# EtherIOv3.net
KiCad netlist of a schematic drawn in Altium Designer
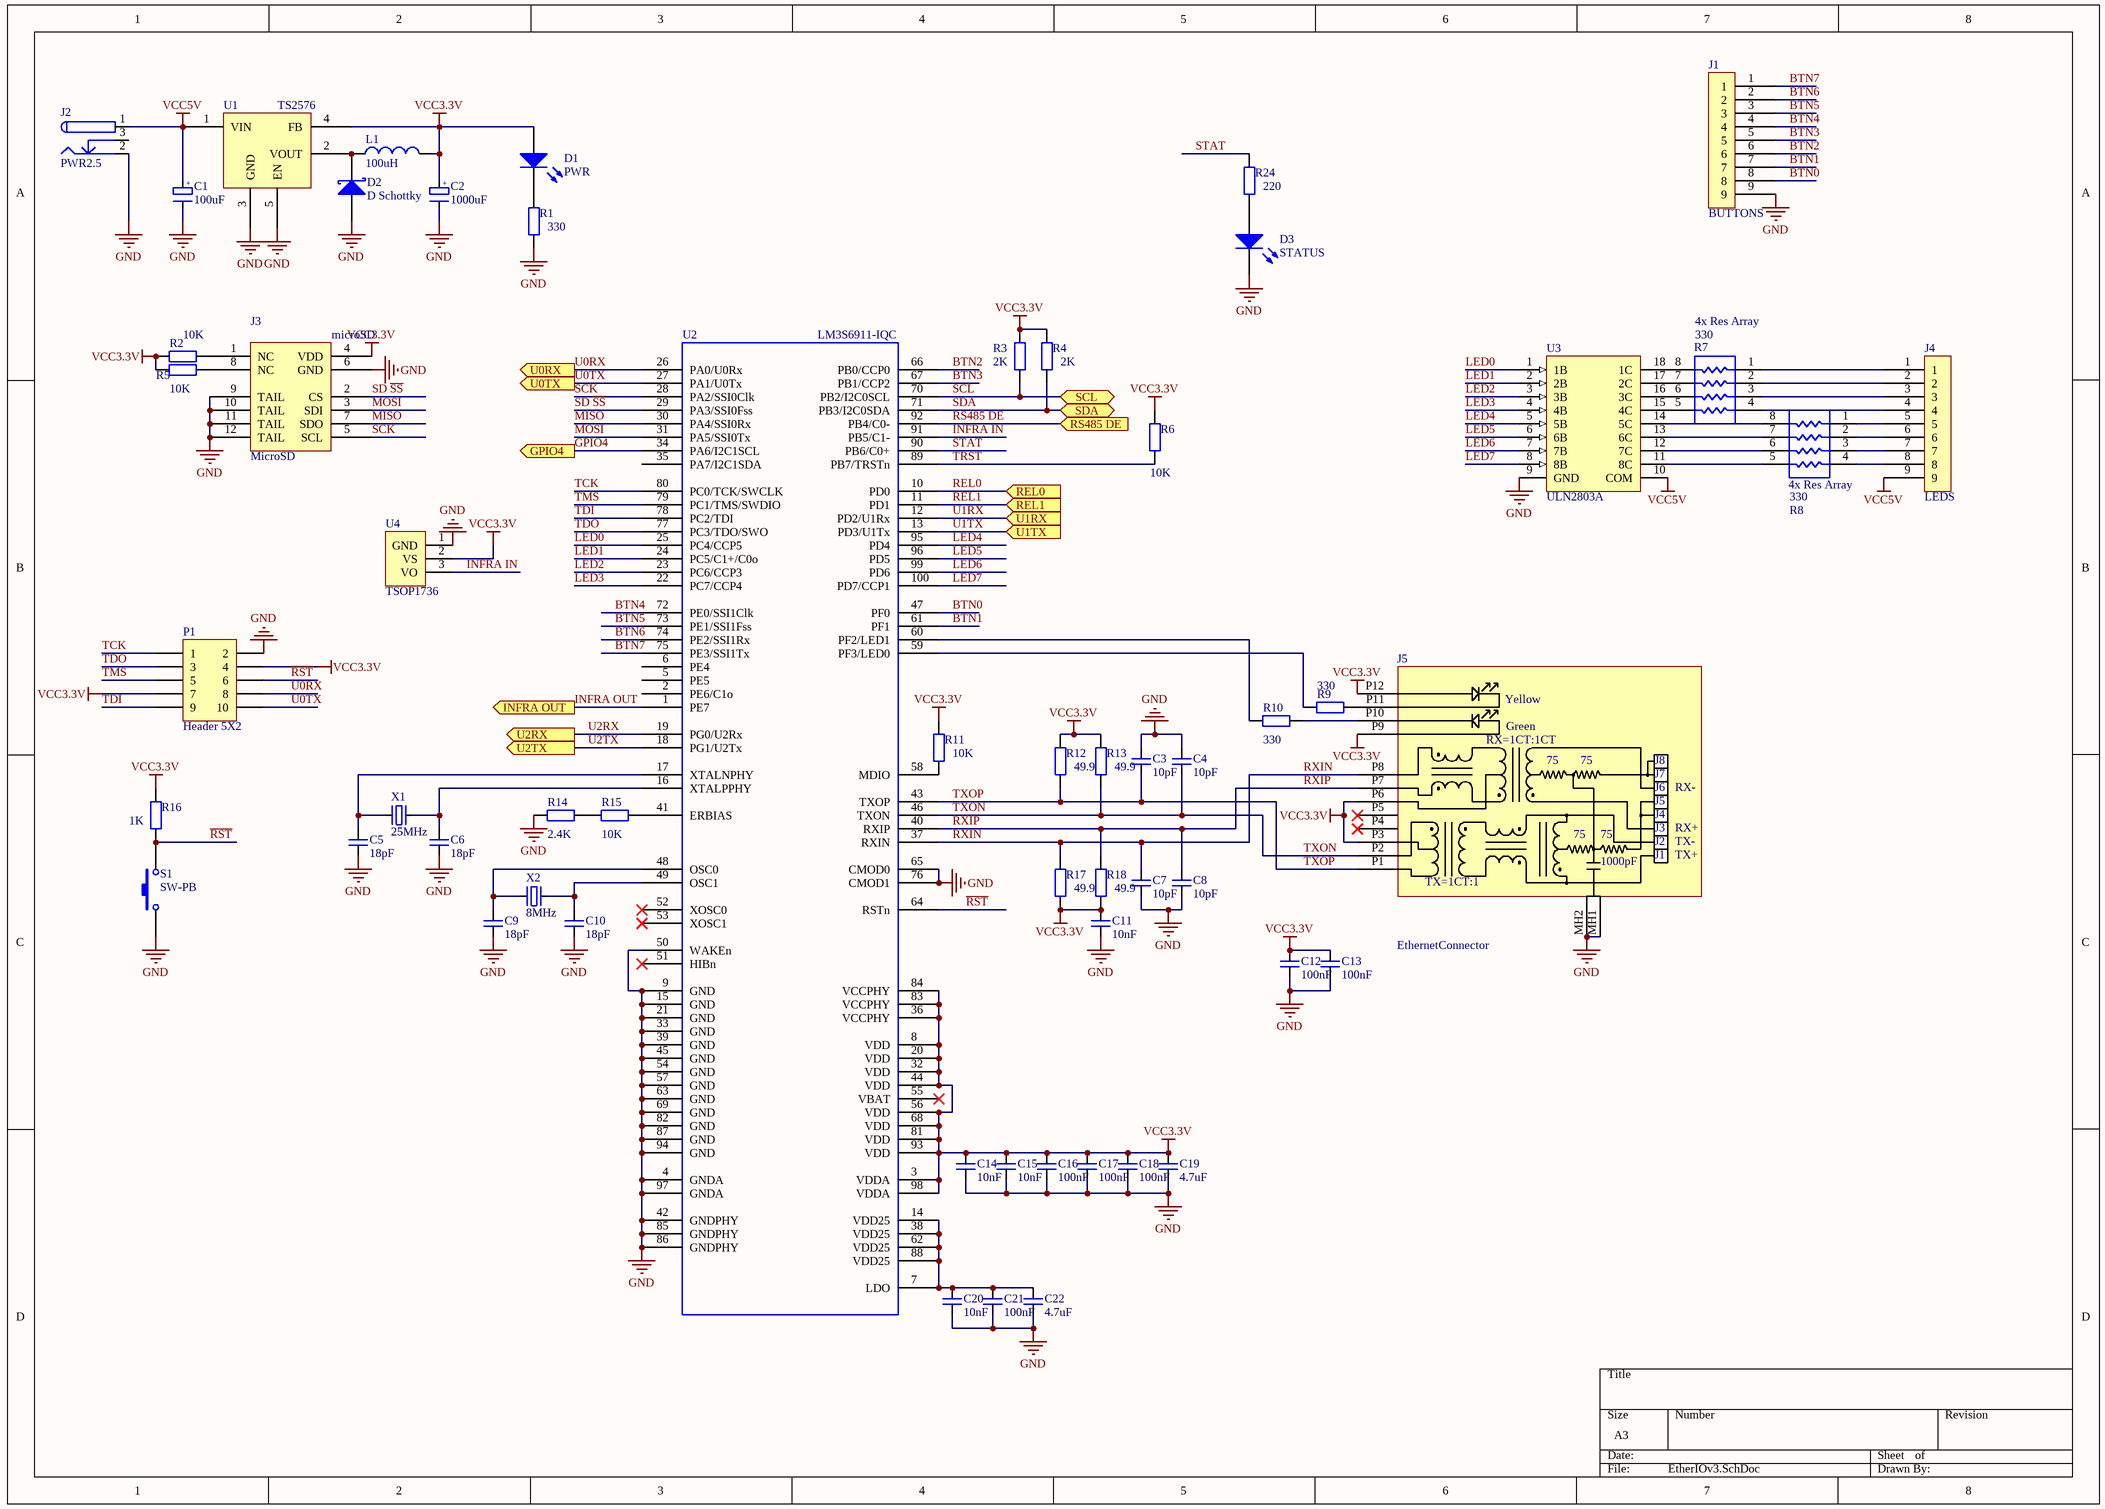
[diagram p0: EtherIOv3.SchDoc]

(export (version "E")
  (design (tool "Eeschema 10.0.6"))
  (components
    (comp (ref "C1")
      (value "100uF")
      (footprint "Electrolit Cap F80")
      (description "SMD Electrolit Capacitor")
      (fields (field (name "Comment") "100uF_25V"))
      (libsource (lib "EtherIOv2") (part "100uF_25V"))
    )
    (comp (ref "C2")
      (value "1000uF")
      (footprint "Electrolit Cap J10")
      (description "SMD Electrolit Capacitor")
      (fields (field (name "Comment") "1000uF_6V3"))
      (libsource (lib "EtherIOv2") (part "1000uF_6V3"))
    )
    (comp (ref "C3")
      (value "10pF")
      (footprint "0805 CAP")
      (description "Capacitor")
      (fields (field (name "Comment") "CAP"))
      (libsource (lib "EtherIOv2") (part "CAP"))
    )
    (comp (ref "C4")
      (value "10pF")
      (footprint "0805 CAP")
      (description "Capacitor")
      (fields (field (name "Comment") "CAP"))
      (libsource (lib "EtherIOv2") (part "CAP"))
    )
    (comp (ref "C5")
      (value "18pF")
      (footprint "0805 CAP")
      (description "Capacitor")
      (fields (field (name "Comment") "CAP"))
      (libsource (lib "EtherIOv2") (part "CAP"))
    )
    (comp (ref "C6")
      (value "18pF")
      (footprint "0805 CAP")
      (description "Capacitor")
      (fields (field (name "Comment") "CAP"))
      (libsource (lib "EtherIOv2") (part "CAP"))
    )
    (comp (ref "C7")
      (value "10pF")
      (footprint "0805 CAP")
      (description "Capacitor")
      (fields (field (name "Comment") "CAP"))
      (libsource (lib "EtherIOv2") (part "CAP"))
    )
    (comp (ref "C8")
      (value "10pF")
      (footprint "0805 CAP")
      (description "Capacitor")
      (fields (field (name "Comment") "CAP"))
      (libsource (lib "EtherIOv2") (part "CAP"))
    )
    (comp (ref "C9")
      (value "18pF")
      (footprint "0805 CAP")
      (description "Capacitor")
      (fields (field (name "Comment") "CAP"))
      (libsource (lib "EtherIOv2") (part "CAP"))
    )
    (comp (ref "C10")
      (value "18pF")
      (footprint "0805 CAP")
      (description "Capacitor")
      (fields (field (name "Comment") "CAP"))
      (libsource (lib "EtherIOv2") (part "CAP"))
    )
    (comp (ref "C11")
      (value "10nF")
      (footprint "0805 CAP")
      (description "Capacitor")
      (fields (field (name "Comment") "CAP"))
      (libsource (lib "EtherIOv2") (part "CAP"))
    )
    (comp (ref "C12")
      (value "100nF")
      (footprint "0805 CAP")
      (description "Capacitor")
      (fields (field (name "Comment") "CAP"))
      (libsource (lib "EtherIOv2") (part "CAP"))
    )
    (comp (ref "C13")
      (value "100nF")
      (footprint "0805 CAP")
      (description "Capacitor")
      (fields (field (name "Comment") "CAP"))
      (libsource (lib "EtherIOv2") (part "CAP"))
    )
    (comp (ref "C14")
      (value "10nF")
      (footprint "0805 CAP")
      (description "Capacitor")
      (fields (field (name "Comment") "CAP"))
      (libsource (lib "EtherIOv2") (part "CAP"))
    )
    (comp (ref "C15")
      (value "10nF")
      (footprint "0805 CAP")
      (description "Capacitor")
      (fields (field (name "Comment") "CAP"))
      (libsource (lib "EtherIOv2") (part "CAP"))
    )
    (comp (ref "C16")
      (value "100nF")
      (footprint "0805 CAP")
      (description "Capacitor")
      (fields (field (name "Comment") "CAP"))
      (libsource (lib "EtherIOv2") (part "CAP"))
    )
    (comp (ref "C17")
      (value "100nF")
      (footprint "0805 CAP")
      (description "Capacitor")
      (fields (field (name "Comment") "CAP"))
      (libsource (lib "EtherIOv2") (part "CAP"))
    )
    (comp (ref "C18")
      (value "100nF")
      (footprint "0805 CAP")
      (description "Capacitor")
      (fields (field (name "Comment") "CAP"))
      (libsource (lib "EtherIOv2") (part "CAP"))
    )
    (comp (ref "C19")
      (value "4.7uF")
      (footprint "0805 CAP")
      (description "Capacitor")
      (fields (field (name "Comment") "CAP"))
      (libsource (lib "EtherIOv2") (part "CAP"))
    )
    (comp (ref "C20")
      (value "10nF")
      (footprint "0805 CAP")
      (description "Capacitor")
      (fields (field (name "Comment") "CAP"))
      (libsource (lib "EtherIOv2") (part "CAP"))
    )
    (comp (ref "C21")
      (value "100nF")
      (footprint "0805 CAP")
      (description "Capacitor")
      (fields (field (name "Comment") "CAP"))
      (libsource (lib "EtherIOv2") (part "CAP"))
    )
    (comp (ref "C22")
      (value "4.7uF")
      (footprint "0805 CAP")
      (description "Capacitor")
      (fields (field (name "Comment") "CAP"))
      (libsource (lib "EtherIOv2") (part "CAP"))
    )
    (comp (ref "D1")
      (value "PWR")
      (footprint "0805 LED")
      (description "Typical RED, GREEN, YELLOW, AMBER GaAs LED")
      (fields (field (name "PUBLISHER") "Altium Limited"))
      (libsource (lib "Miscellaneous Devices") (part "LED2"))
    )
    (comp (ref "D2")
      (value "D Schottky")
      (footprint "DSO-C2/X2.3")
      (description "Schottky Diode")
      (fields (field (name "PUBLISHER") "Altium Limited"))
      (libsource (lib "Miscellaneous Devices") (part "D Schottky"))
    )
    (comp (ref "D3")
      (value "STATUS")
      (footprint "LED-1")
      (description "Typical RED GaAs LED")
      (fields (field (name "PUBLISHER") "Altium Limited"))
      (libsource (lib "Miscellaneous Devices") (part "LED1"))
    )
    (comp (ref "J1")
      (value "BUTTONS")
      (footprint "Euroblock 3.5pitch 9P")
      (libsource (lib "EtherIOv2") (part "Euroblock 9P connector"))
    )
    (comp (ref "J2")
      (value "PWR2.5")
      (footprint "KLD-0202")
      (description "Low Voltage Power Supply Connector")
      (fields (field (name "PUBLISHER") "Altium Limited"))
      (libsource (lib "EtherIOv2") (part "PWR2.5"))
    )
    (comp (ref "J3") (value "MicroSD") (footprint "microSD") (libsource (lib "Waterstars") (part "MicroSD")))
    (comp (ref "J4")
      (value "LEDS")
      (footprint "Euroblock 3.5pitch 9P")
      (libsource (lib "") (part "Euroblock 9P connector_1"))
    )
    (comp (ref "J5")
      (value "EthernetConnector")
      (footprint "LU1T516-43")
      (libsource (lib "EtherIOv2") (part "EthernetConnector"))
    )
    (comp (ref "L1")
      (value "100uH")
      (footprint "INDP127127X85N")
      (description "Inductor")
      (fields (field (name "PUBLISHER") "Altium Limited"))
      (libsource (lib "Miscellaneous Devices") (part "Inductor"))
    )
    (comp (ref "P1")
      (value "Header 5X2")
      (footprint "IDC2.54-V10D")
      (description "Header, 5-Pin, Dual row")
      (fields (field (name "PUBLISHER") "Altium Limited"))
      (libsource (lib "EtherIOv2") (part "Header 5X2"))
    )
    (comp (ref "R1")
      (value "330")
      (footprint "0805 RES")
      (description "Resistor")
      (fields (field (name "Comment") "RES") (field (name "PUBLISHER") "Altium Limited"))
      (libsource (lib "") (part "RES_1"))
    )
    (comp (ref "R2")
      (value "10K")
      (footprint "0805 RES")
      (description "Resistor")
      (fields (field (name "Comment") "RES") (field (name "PUBLISHER") "Altium Limited"))
      (libsource (lib "EtherIOv2") (part "RES"))
    )
    (comp (ref "R3")
      (value "2K")
      (footprint "0805 RES")
      (description "Resistor")
      (fields (field (name "Comment") "RES") (field (name "PUBLISHER") "Altium Limited"))
      (libsource (lib "") (part "RES_1"))
    )
    (comp (ref "R4")
      (value "2K")
      (footprint "0805 RES")
      (description "Resistor")
      (fields (field (name "Comment") "RES") (field (name "PUBLISHER") "Altium Limited"))
      (libsource (lib "") (part "RES_1"))
    )
    (comp (ref "R5")
      (value "10K")
      (footprint "0805 RES")
      (description "Resistor")
      (fields (field (name "Comment") "RES") (field (name "PUBLISHER") "Altium Limited"))
      (libsource (lib "EtherIOv2") (part "RES"))
    )
    (comp (ref "R6")
      (value "10K")
      (footprint "0805 RES")
      (description "Resistor")
      (fields (field (name "Comment") "RES") (field (name "PUBLISHER") "Altium Limited"))
      (libsource (lib "") (part "RES_1"))
    )
    (comp (ref "R7")
      (value "4x Res Array")
      (footprint "1206 4xRES ARRAY")
      (description "Isolated Resistor Network")
      (fields (field (name "ALTIUM_VALUE") "330") (field (name "PUBLISHER") "Altium Limited"))
      (libsource (lib "EtherIOv2") (part "4x Res Array"))
    )
    (comp (ref "R8")
      (value "4x Res Array")
      (footprint "1206 4xRES ARRAY")
      (description "Isolated Resistor Network")
      (fields (field (name "ALTIUM_VALUE") "330") (field (name "PUBLISHER") "Altium Limited"))
      (libsource (lib "EtherIOv2") (part "4x Res Array"))
    )
    (comp (ref "R9")
      (value "330")
      (footprint "0805 RES")
      (description "Resistor")
      (fields (field (name "Comment") "RES") (field (name "PUBLISHER") "Altium Limited"))
      (libsource (lib "") (part "RES_2"))
    )
    (comp (ref "R10")
      (value "330")
      (footprint "0805 RES")
      (description "Resistor")
      (fields (field (name "Comment") "RES") (field (name "PUBLISHER") "Altium Limited"))
      (libsource (lib "") (part "RES_2"))
    )
    (comp (ref "R11")
      (value "10K")
      (footprint "0805 RES")
      (description "Resistor")
      (fields (field (name "Comment") "RES") (field (name "PUBLISHER") "Altium Limited"))
      (libsource (lib "") (part "RES_1"))
    )
    (comp (ref "R12")
      (value "49.9")
      (footprint "0805 RES")
      (description "Resistor")
      (fields (field (name "Comment") "RES") (field (name "PUBLISHER") "Altium Limited"))
      (libsource (lib "") (part "RES_1"))
    )
    (comp (ref "R13")
      (value "49.9")
      (footprint "0805 RES")
      (description "Resistor")
      (fields (field (name "Comment") "RES") (field (name "PUBLISHER") "Altium Limited"))
      (libsource (lib "") (part "RES_1"))
    )
    (comp (ref "R14")
      (value "2.4K")
      (footprint "0805 RES")
      (description "Resistor")
      (fields (field (name "Comment") "RES") (field (name "PUBLISHER") "Altium Limited"))
      (libsource (lib "") (part "RES_2"))
    )
    (comp (ref "R15")
      (value "10K")
      (footprint "0805 RES")
      (description "Resistor")
      (fields (field (name "Comment") "RES") (field (name "PUBLISHER") "Altium Limited"))
      (libsource (lib "") (part "RES_2"))
    )
    (comp (ref "R16")
      (value "1K")
      (footprint "0805 RES")
      (description "Resistor")
      (fields (field (name "Comment") "RES") (field (name "PUBLISHER") "Altium Limited"))
      (libsource (lib "") (part "RES_1"))
    )
    (comp (ref "R17")
      (value "49.9")
      (footprint "0805 RES")
      (description "Resistor")
      (fields (field (name "Comment") "RES") (field (name "PUBLISHER") "Altium Limited"))
      (libsource (lib "") (part "RES_3"))
    )
    (comp (ref "R18")
      (value "49.9")
      (footprint "0805 RES")
      (description "Resistor")
      (fields (field (name "Comment") "RES") (field (name "PUBLISHER") "Altium Limited"))
      (libsource (lib "") (part "RES_3"))
    )
    (comp (ref "R24")
      (value "220")
      (footprint "0805 RES")
      (description "Resistor")
      (fields (field (name "Comment") "RES") (field (name "PUBLISHER") "Altium Limited"))
      (libsource (lib "") (part "RES_1"))
    )
    (comp (ref "S1")
      (value "SW-PB")
      (footprint "SPST-2")
      (description "Switch")
      (fields (field (name "PUBLISHER") "Altium Limited"))
      (libsource (lib "EtherIOv2") (part "SW-PB"))
    )
    (comp (ref "U1")
      (value "TS2576")
      (footprint "TO-263-5L")
      (description "Step Down DC-DC Converter")
      (libsource (lib "EtherIOv2") (part "TS2576"))
    )
    (comp (ref "U2")
      (value "LM3S6911-IQC")
      (footprint "Luminary+Micro:QFP50P1600X1600X160-100N")
      (description "Stellaris ARM Cortex-M3 Microcontroller")
      (fields (field (name "MFG") "Luminary Micro"))
      (libsource (lib "Luminary+Micro") (part "LM3S6611-IQC"))
    )
    (comp (ref "U3")
      (value "ULN2803A")
      (footprint "SOIC127P1030X265-18N")
      (description "8xDarlington Driver")
      (libsource (lib "EtherIOv2") (part "ULN2803A"))
    )
    (comp (ref "U4")
      (value "TSOP1736")
      (footprint "TSOP17xx")
      (description "IR Receiver, 3-Pin")
      (fields (field (name "PUBLISHER") "Altium Limited"))
      (libsource (lib "EtherIOv2") (part "TSOP17xx"))
    )
    (comp (ref "X1")
      (value "25MHz")
      (footprint "CRYSTAL_LOW")
      (description "Crystal")
      (fields (field (name "Comment") "CRYSTAL"))
      (libsource (lib "EtherIOv2") (part "CRYSTAL"))
    )
    (comp (ref "X2")
      (value "8MHz")
      (footprint "CRYSTAL_LOW")
      (description "Crystal")
      (fields (field (name "Comment") "CRYSTAL"))
      (libsource (lib "EtherIOv2") (part "CRYSTAL"))
    )
  )
  (nets
    (net (code "1") (name "/BTN0") (class "Default")
      (node (ref "J1") (pin "8") (pinfunction "8_8") (pintype "passive"))
      (node (ref "U2") (pin "47") (pinfunction "PF0_47") (pintype "passive"))
    )
    (net (code "2") (name "/BTN1") (class "Default")
      (node (ref "J1") (pin "7") (pinfunction "7_7") (pintype "passive"))
      (node (ref "U2") (pin "61") (pinfunction "PF1_61") (pintype "passive"))
    )
    (net (code "3") (name "/BTN2") (class "Default")
      (node (ref "J1") (pin "6") (pinfunction "6_6") (pintype "passive"))
      (node (ref "U2") (pin "66") (pinfunction "PB0/CCP0_66") (pintype "passive"))
    )
    (net (code "4") (name "/BTN3") (class "Default")
      (node (ref "J1") (pin "5") (pinfunction "5_5") (pintype "passive"))
      (node (ref "U2") (pin "67") (pinfunction "PB1/CCP2_67") (pintype "passive"))
    )
    (net (code "5") (name "/BTN4") (class "Default")
      (node (ref "J1") (pin "4") (pinfunction "4_4") (pintype "passive"))
      (node (ref "U2") (pin "72") (pinfunction "PE0/SSI1Clk_72") (pintype "passive"))
    )
    (net (code "6") (name "/BTN5") (class "Default")
      (node (ref "J1") (pin "3") (pinfunction "3_3") (pintype "passive"))
      (node (ref "U2") (pin "73") (pinfunction "PE1/SSI1Fss_73") (pintype "passive"))
    )
    (net (code "7") (name "/BTN6") (class "Default")
      (node (ref "J1") (pin "2") (pinfunction "2_2") (pintype "passive"))
      (node (ref "U2") (pin "74") (pinfunction "PE2/SSI1Rx_74") (pintype "passive"))
    )
    (net (code "8") (name "/BTN7") (class "Default")
      (node (ref "J1") (pin "1") (pinfunction "1_1") (pintype "passive"))
      (node (ref "U2") (pin "75") (pinfunction "PE3/SSI1Tx_75") (pintype "passive"))
    )
    (net (code "9") (name "/GPIO4") (class "Default")
      (node (ref "U2") (pin "34") (pinfunction "PA6/I2C1SCL_34") (pintype "passive"))
    )
    (net (code "10") (name "/INFRA IN") (class "Default")
      (node (ref "U2") (pin "91") (pinfunction "PB5/C1-_91") (pintype "passive"))
      (node (ref "U4") (pin "3") (pinfunction "VO_3") (pintype "passive"))
    )
    (net (code "11") (name "/INFRA OUT") (class "Default")
      (node (ref "U2") (pin "1") (pinfunction "PE7_1") (pintype "passive"))
    )
    (net (code "12") (name "/LED0") (class "Default")
      (node (ref "U2") (pin "25") (pinfunction "PC4/CCP5_25") (pintype "passive"))
      (node (ref "U3") (pin "1") (pinfunction "1B_1") (pintype "input"))
    )
    (net (code "13") (name "/LED1") (class "Default")
      (node (ref "U2") (pin "24") (pinfunction "PC5/C1+/C0o_24") (pintype "passive"))
      (node (ref "U3") (pin "2") (pinfunction "2B_2") (pintype "input"))
    )
    (net (code "14") (name "/LED2") (class "Default")
      (node (ref "U2") (pin "23") (pinfunction "PC6/CCP3_23") (pintype "passive"))
      (node (ref "U3") (pin "3") (pinfunction "3B_3") (pintype "input"))
    )
    (net (code "15") (name "/LED3") (class "Default")
      (node (ref "U2") (pin "22") (pinfunction "PC7/CCP4_22") (pintype "passive"))
      (node (ref "U3") (pin "4") (pinfunction "4B_4") (pintype "input"))
    )
    (net (code "16") (name "/LED4") (class "Default")
      (node (ref "U2") (pin "95") (pinfunction "PD4_95") (pintype "passive"))
      (node (ref "U3") (pin "5") (pinfunction "5B_5") (pintype "input"))
    )
    (net (code "17") (name "/LED5") (class "Default")
      (node (ref "U2") (pin "96") (pinfunction "PD5_96") (pintype "passive"))
      (node (ref "U3") (pin "6") (pinfunction "6B_6") (pintype "input"))
    )
    (net (code "18") (name "/LED6") (class "Default")
      (node (ref "U2") (pin "99") (pinfunction "PD6_99") (pintype "passive"))
      (node (ref "U3") (pin "7") (pinfunction "7B_7") (pintype "input"))
    )
    (net (code "19") (name "/LED7") (class "Default")
      (node (ref "U2") (pin "100") (pinfunction "PD7/CCP1_100") (pintype "passive"))
      (node (ref "U3") (pin "8") (pinfunction "8B_8") (pintype "input"))
    )
    (net (code "20") (name "/MISO") (class "Default")
      (node (ref "J3") (pin "7") (pinfunction "SDO_7") (pintype "passive"))
      (node (ref "U2") (pin "30") (pinfunction "PA4/SSI0Rx_30") (pintype "passive"))
    )
    (net (code "21") (name "/MOSI") (class "Default")
      (node (ref "J3") (pin "3") (pinfunction "SDI_3") (pintype "passive"))
      (node (ref "U2") (pin "31") (pinfunction "PA5/SSI0Tx_31") (pintype "passive"))
    )
    (net (code "22") (name "/REL0") (class "Default")
      (node (ref "U2") (pin "10") (pinfunction "PD0_10") (pintype "passive"))
    )
    (net (code "23") (name "/REL1") (class "Default")
      (node (ref "U2") (pin "11") (pinfunction "PD1_11") (pintype "passive"))
    )
    (net (code "24") (name "/RS485 DE") (class "Default")
      (node (ref "U2") (pin "92") (pinfunction "PB4/C0-_92") (pintype "passive"))
    )
    (net (code "25") (name "/RXIN") (class "Default")
      (node (ref "C7") (pin "1") (pinfunction "A_1") (pintype "passive"))
      (node (ref "J5") (pin "P8") (pinfunction "P8_P8") (pintype "passive"))
      (node (ref "R17") (pin "1") (pinfunction "1_1") (pintype "passive"))
      (node (ref "U2") (pin "37") (pinfunction "RXIN_37") (pintype "passive"))
    )
    (net (code "26") (name "/RXIP") (class "Default")
      (node (ref "C8") (pin "1") (pinfunction "A_1") (pintype "passive"))
      (node (ref "J5") (pin "P7") (pinfunction "P7_P7") (pintype "passive"))
      (node (ref "R18") (pin "1") (pinfunction "1_1") (pintype "passive"))
      (node (ref "U2") (pin "40") (pinfunction "RXIP_40") (pintype "passive"))
    )
    (net (code "27") (name "/SCK") (class "Default")
      (node (ref "J3") (pin "5") (pinfunction "SCL_5") (pintype "passive"))
      (node (ref "U2") (pin "28") (pinfunction "PA2/SSI0Clk_28") (pintype "passive"))
    )
    (net (code "28") (name "/SCL") (class "Default")
      (node (ref "R3") (pin "1") (pinfunction "1_1") (pintype "passive"))
      (node (ref "U2") (pin "70") (pinfunction "PB2/I2C0SCL_70") (pintype "passive"))
    )
    (net (code "29") (name "/SD ~{SS}") (class "Default")
      (node (ref "J3") (pin "2") (pinfunction "CS_2") (pintype "passive"))
      (node (ref "U2") (pin "29") (pinfunction "PA3/SSI0Fss_29") (pintype "passive"))
    )
    (net (code "30") (name "/SDA") (class "Default")
      (node (ref "R4") (pin "1") (pinfunction "1_1") (pintype "passive"))
      (node (ref "U2") (pin "71") (pinfunction "PB3/I2C0SDA_71") (pintype "passive"))
    )
    (net (code "31") (name "/STAT") (class "Default")
      (node (ref "R24") (pin "2") (pinfunction "2_2") (pintype "passive"))
      (node (ref "U2") (pin "90") (pinfunction "PB6/C0+_90") (pintype "passive"))
    )
    (net (code "32") (name "/TCK") (class "Default")
      (node (ref "P1") (pin "1") (pinfunction "1_1") (pintype "passive"))
      (node (ref "U2") (pin "80") (pinfunction "PC0/TCK/SWCLK_80") (pintype "passive"))
    )
    (net (code "33") (name "/TDI") (class "Default")
      (node (ref "P1") (pin "9") (pinfunction "9_9") (pintype "passive"))
      (node (ref "U2") (pin "78") (pinfunction "PC2/TDI_78") (pintype "passive"))
    )
    (net (code "34") (name "/TDO") (class "Default")
      (node (ref "P1") (pin "3") (pinfunction "3_3") (pintype "passive"))
      (node (ref "U2") (pin "77") (pinfunction "PC3/TDO/SWO_77") (pintype "passive"))
    )
    (net (code "35") (name "/TMS") (class "Default")
      (node (ref "P1") (pin "5") (pinfunction "5_5") (pintype "passive"))
      (node (ref "U2") (pin "79") (pinfunction "PC1/TMS/SWDIO_79") (pintype "passive"))
    )
    (net (code "36") (name "/TXON") (class "Default")
      (node (ref "C4") (pin "1") (pinfunction "A_1") (pintype "passive"))
      (node (ref "J5") (pin "P2") (pinfunction "P2_P2") (pintype "passive"))
      (node (ref "R13") (pin "1") (pinfunction "1_1") (pintype "passive"))
      (node (ref "U2") (pin "46") (pinfunction "TXON_46") (pintype "passive"))
    )
    (net (code "37") (name "/TXOP") (class "Default")
      (node (ref "C3") (pin "1") (pinfunction "A_1") (pintype "passive"))
      (node (ref "J5") (pin "P1") (pinfunction "P1_P1") (pintype "passive"))
      (node (ref "R12") (pin "1") (pinfunction "1_1") (pintype "passive"))
      (node (ref "U2") (pin "43") (pinfunction "TXOP_43") (pintype "passive"))
    )
    (net (code "38") (name "/U0RX") (class "Default")
      (node (ref "P1") (pin "8") (pinfunction "8_8") (pintype "passive"))
      (node (ref "U2") (pin "26") (pinfunction "PA0/U0Rx_26") (pintype "passive"))
    )
    (net (code "39") (name "/U0TX") (class "Default")
      (node (ref "P1") (pin "10") (pinfunction "10_10") (pintype "passive"))
      (node (ref "U2") (pin "27") (pinfunction "PA1/U0Tx_27") (pintype "passive"))
    )
    (net (code "40") (name "/U1RX") (class "Default")
      (node (ref "U2") (pin "12") (pinfunction "PD2/U1Rx_12") (pintype "passive"))
    )
    (net (code "41") (name "/U1TX") (class "Default")
      (node (ref "U2") (pin "13") (pinfunction "PD3/U1Tx_13") (pintype "passive"))
    )
    (net (code "42") (name "/U2RX") (class "Default")
      (node (ref "U2") (pin "19") (pinfunction "PG0/U2Rx_19") (pintype "passive"))
    )
    (net (code "43") (name "/U2TX") (class "Default")
      (node (ref "U2") (pin "18") (pinfunction "PG1/U2Tx_18") (pintype "passive"))
    )
    (net (code "44") (name "/~{RST}") (class "Default")
      (node (ref "P1") (pin "6") (pinfunction "6_6") (pintype "passive"))
      (node (ref "R16") (pin "1") (pinfunction "1_1") (pintype "passive"))
      (node (ref "S1") (pin "2") (pinfunction "2_2") (pintype "passive"))
      (node (ref "U2") (pin "64") (pinfunction "RSTn_64") (pintype "passive"))
    )
    (net (code "45") (name "/~{TRST}") (class "Default")
      (node (ref "R6") (pin "1") (pinfunction "1_1") (pintype "passive"))
      (node (ref "U2") (pin "89") (pinfunction "PB7/TRSTn_89") (pintype "passive"))
    )
    (net (code "46") (name "GND") (class "Default")
      (node (ref "C1") (pin "1") (pinfunction "B_1") (pintype "passive"))
      (node (ref "C10") (pin "1") (pinfunction "A_1") (pintype "passive"))
      (node (ref "C11") (pin "1") (pinfunction "A_1") (pintype "passive"))
      (node (ref "C12") (pin "2") (pinfunction "B_2") (pintype "passive"))
      (node (ref "C13") (pin "2") (pinfunction "B_2") (pintype "passive"))
      (node (ref "C14") (pin "1") (pinfunction "A_1") (pintype "passive"))
      (node (ref "C15") (pin "1") (pinfunction "A_1") (pintype "passive"))
      (node (ref "C16") (pin "1") (pinfunction "A_1") (pintype "passive"))
      (node (ref "C17") (pin "1") (pinfunction "A_1") (pintype "passive"))
      (node (ref "C18") (pin "1") (pinfunction "A_1") (pintype "passive"))
      (node (ref "C19") (pin "1") (pinfunction "A_1") (pintype "passive"))
      (node (ref "C2") (pin "1") (pinfunction "B_1") (pintype "passive"))
      (node (ref "C20") (pin "1") (pinfunction "A_1") (pintype "passive"))
      (node (ref "C21") (pin "1") (pinfunction "A_1") (pintype "passive"))
      (node (ref "C22") (pin "1") (pinfunction "A_1") (pintype "passive"))
      (node (ref "C3") (pin "2") (pinfunction "B_2") (pintype "passive"))
      (node (ref "C4") (pin "2") (pinfunction "B_2") (pintype "passive"))
      (node (ref "C5") (pin "1") (pinfunction "A_1") (pintype "passive"))
      (node (ref "C6") (pin "1") (pinfunction "A_1") (pintype "passive"))
      (node (ref "C7") (pin "2") (pinfunction "B_2") (pintype "passive"))
      (node (ref "C8") (pin "2") (pinfunction "B_2") (pintype "passive"))
      (node (ref "C9") (pin "1") (pinfunction "A_1") (pintype "passive"))
      (node (ref "D2") (pin "1") (pinfunction "A_1") (pintype "passive"))
      (node (ref "D3") (pin "2") (pinfunction "K_2") (pintype "passive"))
      (node (ref "J1") (pin "9") (pinfunction "9_9") (pintype "passive"))
      (node (ref "J2") (pin "2") (pinfunction "2_2") (pintype "passive"))
      (node (ref "J3") (pin "10") (pinfunction "TAIL_10") (pintype "passive"))
      (node (ref "J3") (pin "11") (pinfunction "TAIL_11") (pintype "passive"))
      (node (ref "J3") (pin "12") (pinfunction "TAIL_12") (pintype "passive"))
      (node (ref "J3") (pin "6") (pinfunction "GND_6") (pintype "passive"))
      (node (ref "J3") (pin "9") (pinfunction "TAIL_9") (pintype "passive"))
      (node (ref "J5") (pin "MH1") (pinfunction "SHIELD_MH1") (pintype "passive"))
      (node (ref "J5") (pin "MH2") (pinfunction "SHIELD_MH2") (pintype "passive"))
      (node (ref "P1") (pin "2") (pinfunction "2_2") (pintype "passive"))
      (node (ref "R1") (pin "1") (pinfunction "1_1") (pintype "passive"))
      (node (ref "R14") (pin "1") (pinfunction "1_1") (pintype "passive"))
      (node (ref "S1") (pin "1") (pinfunction "1_1") (pintype "passive"))
      (node (ref "U1") (pin "3") (pinfunction "GND_3") (pintype "power_in"))
      (node (ref "U1") (pin "5") (pinfunction "EN_5") (pintype "passive"))
      (node (ref "U2") (pin "15") (pinfunction "GND_15") (pintype "passive"))
      (node (ref "U2") (pin "21") (pinfunction "GND_21") (pintype "passive"))
      (node (ref "U2") (pin "33") (pinfunction "GND_33") (pintype "passive"))
      (node (ref "U2") (pin "39") (pinfunction "GND_39") (pintype "passive"))
      (node (ref "U2") (pin "4") (pinfunction "GNDA_4") (pintype "passive"))
      (node (ref "U2") (pin "42") (pinfunction "GNDPHY_42") (pintype "passive"))
      (node (ref "U2") (pin "45") (pinfunction "GND_45") (pintype "passive"))
      (node (ref "U2") (pin "50") (pinfunction "WAKEn_50") (pintype "passive"))
      (node (ref "U2") (pin "54") (pinfunction "GND_54") (pintype "passive"))
      (node (ref "U2") (pin "57") (pinfunction "GND_57") (pintype "passive"))
      (node (ref "U2") (pin "63") (pinfunction "GND_63") (pintype "passive"))
      (node (ref "U2") (pin "65") (pinfunction "CMOD0_65") (pintype "passive"))
      (node (ref "U2") (pin "69") (pinfunction "GND_69") (pintype "passive"))
      (node (ref "U2") (pin "76") (pinfunction "CMOD1_76") (pintype "passive"))
      (node (ref "U2") (pin "82") (pinfunction "GND_82") (pintype "passive"))
      (node (ref "U2") (pin "85") (pinfunction "GNDPHY_85") (pintype "passive"))
      (node (ref "U2") (pin "86") (pinfunction "GNDPHY_86") (pintype "passive"))
      (node (ref "U2") (pin "87") (pinfunction "GND_87") (pintype "passive"))
      (node (ref "U2") (pin "9") (pinfunction "GND_9") (pintype "passive"))
      (node (ref "U2") (pin "94") (pinfunction "GND_94") (pintype "passive"))
      (node (ref "U2") (pin "97") (pinfunction "GNDA_97") (pintype "passive"))
      (node (ref "U3") (pin "9") (pinfunction "GND_9") (pintype "power_in"))
      (node (ref "U4") (pin "1") (pinfunction "GND_1") (pintype "passive"))
    )
    (net (code "47") (name "Net-(C5-B)") (class "Default")
      (node (ref "C5") (pin "2") (pinfunction "B_2") (pintype "passive"))
      (node (ref "U2") (pin "17") (pinfunction "XTALNPHY_17") (pintype "passive"))
      (node (ref "X1") (pin "1") (pinfunction "A_1") (pintype "passive"))
    )
    (net (code "48") (name "Net-(C6-B)") (class "Default")
      (node (ref "C6") (pin "2") (pinfunction "B_2") (pintype "passive"))
      (node (ref "U2") (pin "16") (pinfunction "XTALPPHY_16") (pintype "passive"))
      (node (ref "X1") (pin "2") (pinfunction "B_2") (pintype "passive"))
    )
    (net (code "49") (name "Net-(C9-B)") (class "Default")
      (node (ref "C9") (pin "2") (pinfunction "B_2") (pintype "passive"))
      (node (ref "U2") (pin "48") (pinfunction "OSC0_48") (pintype "passive"))
      (node (ref "X2") (pin "1") (pinfunction "A_1") (pintype "passive"))
    )
    (net (code "50") (name "Net-(C10-B)") (class "Default")
      (node (ref "C10") (pin "2") (pinfunction "B_2") (pintype "passive"))
      (node (ref "U2") (pin "49") (pinfunction "OSC1_49") (pintype "passive"))
      (node (ref "X2") (pin "2") (pinfunction "B_2") (pintype "passive"))
    )
    (net (code "51") (name "Net-(C20-B)") (class "Default")
      (node (ref "C20") (pin "2") (pinfunction "B_2") (pintype "passive"))
      (node (ref "C21") (pin "2") (pinfunction "B_2") (pintype "passive"))
      (node (ref "C22") (pin "2") (pinfunction "B_2") (pintype "passive"))
      (node (ref "U2") (pin "14") (pinfunction "VDD25_14") (pintype "passive"))
      (node (ref "U2") (pin "38") (pinfunction "VDD25_38") (pintype "passive"))
      (node (ref "U2") (pin "62") (pinfunction "VDD25_62") (pintype "passive"))
      (node (ref "U2") (pin "7") (pinfunction "LDO_7") (pintype "passive"))
      (node (ref "U2") (pin "88") (pinfunction "VDD25_88") (pintype "passive"))
    )
    (net (code "52") (name "Net-(D1-K)") (class "Default")
      (node (ref "D1") (pin "2") (pinfunction "K_2") (pintype "passive"))
      (node (ref "R1") (pin "2") (pinfunction "2_2") (pintype "passive"))
    )
    (net (code "53") (name "Net-(D2-K)") (class "Default")
      (node (ref "D2") (pin "2") (pinfunction "K_2") (pintype "passive"))
      (node (ref "L1") (pin "1") (pinfunction "1_1") (pintype "passive"))
      (node (ref "U1") (pin "2") (pinfunction "VOUT_2") (pintype "passive"))
    )
    (net (code "54") (name "Net-(D3-A)") (class "Default")
      (node (ref "D3") (pin "1") (pinfunction "A_1") (pintype "passive"))
      (node (ref "R24") (pin "1") (pinfunction "1_1") (pintype "passive"))
    )
    (net (code "55") (name "Net-(J3-NC-Pad1)") (class "Default")
      (node (ref "J3") (pin "1") (pinfunction "NC_1") (pintype "passive"))
      (node (ref "R2") (pin "1") (pinfunction "1_1") (pintype "passive"))
    )
    (net (code "56") (name "Net-(J3-NC-Pad8)") (class "Default")
      (node (ref "J3") (pin "8") (pinfunction "NC_8") (pintype "passive"))
      (node (ref "R5") (pin "1") (pinfunction "1_1") (pintype "passive"))
    )
    (net (code "57") (name "Net-(J4-Pad1)") (class "Default")
      (node (ref "J4") (pin "1") (pinfunction "1_1") (pintype "passive"))
      (node (ref "R7") (pin "1") (pinfunction "1_1") (pintype "passive"))
    )
    (net (code "58") (name "Net-(J4-Pad2)") (class "Default")
      (node (ref "J4") (pin "2") (pinfunction "2_2") (pintype "passive"))
      (node (ref "R7") (pin "2") (pinfunction "2_2") (pintype "passive"))
    )
    (net (code "59") (name "Net-(J4-Pad3)") (class "Default")
      (node (ref "J4") (pin "3") (pinfunction "3_3") (pintype "passive"))
      (node (ref "R7") (pin "3") (pinfunction "3_3") (pintype "passive"))
    )
    (net (code "60") (name "Net-(J4-Pad4)") (class "Default")
      (node (ref "J4") (pin "4") (pinfunction "4_4") (pintype "passive"))
      (node (ref "R7") (pin "4") (pinfunction "4_4") (pintype "passive"))
    )
    (net (code "61") (name "Net-(J4-Pad5)") (class "Default")
      (node (ref "J4") (pin "5") (pinfunction "5_5") (pintype "passive"))
      (node (ref "R8") (pin "1") (pinfunction "1_1") (pintype "passive"))
    )
    (net (code "62") (name "Net-(J4-Pad6)") (class "Default")
      (node (ref "J4") (pin "6") (pinfunction "6_6") (pintype "passive"))
      (node (ref "R8") (pin "2") (pinfunction "2_2") (pintype "passive"))
    )
    (net (code "63") (name "Net-(J4-Pad7)") (class "Default")
      (node (ref "J4") (pin "7") (pinfunction "7_7") (pintype "passive"))
      (node (ref "R8") (pin "3") (pinfunction "3_3") (pintype "passive"))
    )
    (net (code "64") (name "Net-(J4-Pad8)") (class "Default")
      (node (ref "J4") (pin "8") (pinfunction "8_8") (pintype "passive"))
      (node (ref "R8") (pin "4") (pinfunction "4_4") (pintype "passive"))
    )
    (net (code "65") (name "Net-(J5-PadP10)") (class "Default")
      (node (ref "J5") (pin "P10") (pinfunction "P10_P10") (pintype "passive"))
      (node (ref "R10") (pin "2") (pinfunction "2_2") (pintype "passive"))
    )
    (net (code "66") (name "Net-(J5-PadP11)") (class "Default")
      (node (ref "J5") (pin "P11") (pinfunction "P11_P11") (pintype "passive"))
      (node (ref "R9") (pin "2") (pinfunction "2_2") (pintype "passive"))
    )
    (net (code "67") (name "Net-(R14-Pad2)") (class "Default")
      (node (ref "R14") (pin "2") (pinfunction "2_2") (pintype "passive"))
      (node (ref "R15") (pin "1") (pinfunction "1_1") (pintype "passive"))
    )
    (net (code "68") (name "Net-(U2-ERBIAS)") (class "Default")
      (node (ref "R15") (pin "2") (pinfunction "2_2") (pintype "passive"))
      (node (ref "U2") (pin "41") (pinfunction "ERBIAS_41") (pintype "passive"))
    )
    (net (code "69") (name "Net-(U2-MDIO)") (class "Default")
      (node (ref "R11") (pin "1") (pinfunction "1_1") (pintype "passive"))
      (node (ref "U2") (pin "58") (pinfunction "MDIO_58") (pintype "passive"))
    )
    (net (code "70") (name "Net-(U2-PF2{slash}LED1)") (class "Default")
      (node (ref "R10") (pin "1") (pinfunction "1_1") (pintype "passive"))
      (node (ref "U2") (pin "60") (pinfunction "PF2/LED1_60") (pintype "passive"))
    )
    (net (code "71") (name "Net-(U2-PF3{slash}LED0)") (class "Default")
      (node (ref "R9") (pin "1") (pinfunction "1_1") (pintype "passive"))
      (node (ref "U2") (pin "59") (pinfunction "PF3/LED0_59") (pintype "passive"))
    )
    (net (code "72") (name "Net-(U3-1C)") (class "Default")
      (node (ref "R7") (pin "8") (pinfunction "8_8") (pintype "passive"))
      (node (ref "U3") (pin "18") (pinfunction "1C_18") (pintype "open_collector"))
    )
    (net (code "73") (name "Net-(U3-2C)") (class "Default")
      (node (ref "R7") (pin "7") (pinfunction "7_7") (pintype "passive"))
      (node (ref "U3") (pin "17") (pinfunction "2C_17") (pintype "open_collector"))
    )
    (net (code "74") (name "Net-(U3-3C)") (class "Default")
      (node (ref "R7") (pin "6") (pinfunction "6_6") (pintype "passive"))
      (node (ref "U3") (pin "16") (pinfunction "3C_16") (pintype "open_collector"))
    )
    (net (code "75") (name "Net-(U3-4C)") (class "Default")
      (node (ref "R7") (pin "5") (pinfunction "5_5") (pintype "passive"))
      (node (ref "U3") (pin "15") (pinfunction "4C_15") (pintype "open_collector"))
    )
    (net (code "76") (name "Net-(U3-5C)") (class "Default")
      (node (ref "R8") (pin "8") (pinfunction "8_8") (pintype "passive"))
      (node (ref "U3") (pin "14") (pinfunction "5C_14") (pintype "open_collector"))
    )
    (net (code "77") (name "Net-(U3-6C)") (class "Default")
      (node (ref "R8") (pin "7") (pinfunction "7_7") (pintype "passive"))
      (node (ref "U3") (pin "13") (pinfunction "6C_13") (pintype "open_collector"))
    )
    (net (code "78") (name "Net-(U3-7C)") (class "Default")
      (node (ref "R8") (pin "6") (pinfunction "6_6") (pintype "passive"))
      (node (ref "U3") (pin "12") (pinfunction "7C_12") (pintype "open_collector"))
    )
    (net (code "79") (name "Net-(U3-8C)") (class "Default")
      (node (ref "R8") (pin "5") (pinfunction "5_5") (pintype "passive"))
      (node (ref "U3") (pin "11") (pinfunction "8C_11") (pintype "open_collector"))
    )
    (net (code "80") (name "VCC3.3V") (class "Default")
      (node (ref "C11") (pin "2") (pinfunction "B_2") (pintype "passive"))
      (node (ref "C12") (pin "1") (pinfunction "A_1") (pintype "passive"))
      (node (ref "C13") (pin "1") (pinfunction "A_1") (pintype "passive"))
      (node (ref "C14") (pin "2") (pinfunction "B_2") (pintype "passive"))
      (node (ref "C15") (pin "2") (pinfunction "B_2") (pintype "passive"))
      (node (ref "C16") (pin "2") (pinfunction "B_2") (pintype "passive"))
      (node (ref "C17") (pin "2") (pinfunction "B_2") (pintype "passive"))
      (node (ref "C18") (pin "2") (pinfunction "B_2") (pintype "passive"))
      (node (ref "C19") (pin "2") (pinfunction "B_2") (pintype "passive"))
      (node (ref "C2") (pin "2") (pinfunction "A_2") (pintype "passive"))
      (node (ref "D1") (pin "1") (pinfunction "A_1") (pintype "passive"))
      (node (ref "J3") (pin "4") (pinfunction "VDD_4") (pintype "passive"))
      (node (ref "J5") (pin "P12") (pinfunction "P12_P12") (pintype "passive"))
      (node (ref "J5") (pin "P3") (pinfunction "P3_P3") (pintype "passive"))
      (node (ref "J5") (pin "P6") (pinfunction "P6_P6") (pintype "passive"))
      (node (ref "J5") (pin "P9") (pinfunction "P9_P9") (pintype "passive"))
      (node (ref "L1") (pin "2") (pinfunction "2_2") (pintype "passive"))
      (node (ref "P1") (pin "4") (pinfunction "4_4") (pintype "passive"))
      (node (ref "P1") (pin "7") (pinfunction "7_7") (pintype "passive"))
      (node (ref "R11") (pin "2") (pinfunction "2_2") (pintype "passive"))
      (node (ref "R12") (pin "2") (pinfunction "2_2") (pintype "passive"))
      (node (ref "R13") (pin "2") (pinfunction "2_2") (pintype "passive"))
      (node (ref "R16") (pin "2") (pinfunction "2_2") (pintype "passive"))
      (node (ref "R17") (pin "2") (pinfunction "2_2") (pintype "passive"))
      (node (ref "R18") (pin "2") (pinfunction "2_2") (pintype "passive"))
      (node (ref "R2") (pin "2") (pinfunction "2_2") (pintype "passive"))
      (node (ref "R3") (pin "2") (pinfunction "2_2") (pintype "passive"))
      (node (ref "R4") (pin "2") (pinfunction "2_2") (pintype "passive"))
      (node (ref "R5") (pin "2") (pinfunction "2_2") (pintype "passive"))
      (node (ref "R6") (pin "2") (pinfunction "2_2") (pintype "passive"))
      (node (ref "U1") (pin "4") (pinfunction "FB_4") (pintype "passive"))
      (node (ref "U2") (pin "20") (pinfunction "VDD_20") (pintype "passive"))
      (node (ref "U2") (pin "3") (pinfunction "VDDA_3") (pintype "passive"))
      (node (ref "U2") (pin "32") (pinfunction "VDD_32") (pintype "passive"))
      (node (ref "U2") (pin "36") (pinfunction "VCCPHY_36") (pintype "passive"))
      (node (ref "U2") (pin "44") (pinfunction "VDD_44") (pintype "passive"))
      (node (ref "U2") (pin "56") (pinfunction "VDD_56") (pintype "passive"))
      (node (ref "U2") (pin "68") (pinfunction "VDD_68") (pintype "passive"))
      (node (ref "U2") (pin "8") (pinfunction "VDD_8") (pintype "passive"))
      (node (ref "U2") (pin "81") (pinfunction "VDD_81") (pintype "passive"))
      (node (ref "U2") (pin "83") (pinfunction "VCCPHY_83") (pintype "passive"))
      (node (ref "U2") (pin "84") (pinfunction "VCCPHY_84") (pintype "passive"))
      (node (ref "U2") (pin "93") (pinfunction "VDD_93") (pintype "passive"))
      (node (ref "U2") (pin "98") (pinfunction "VDDA_98") (pintype "passive"))
      (node (ref "U4") (pin "2") (pinfunction "VS_2") (pintype "passive"))
    )
    (net (code "81") (name "VCC5V") (class "Default")
      (node (ref "C1") (pin "2") (pinfunction "A_2") (pintype "passive"))
      (node (ref "J2") (pin "1") (pinfunction "1_1") (pintype "passive"))
      (node (ref "J4") (pin "9") (pinfunction "9_9") (pintype "passive"))
      (node (ref "U1") (pin "1") (pinfunction "VIN_1") (pintype "power_in"))
      (node (ref "U3") (pin "10") (pinfunction "COM_10") (pintype "power_in"))
    )
    (net (code "82") (name "unconnected-(J2-Pad3)") (class "Default")
      (node (ref "J2") (pin "3") (pinfunction "3_3") (pintype "passive"))
    )
    (net (code "83") (name "unconnected-(J5-PadP4)") (class "Default")
      (node (ref "J5") (pin "P4") (pinfunction "P4_P4") (pintype "passive+no_connect"))
    )
    (net (code "84") (name "unconnected-(J5-PadP5)") (class "Default")
      (node (ref "J5") (pin "P5") (pinfunction "P5_P5") (pintype "passive+no_connect"))
    )
    (net (code "85") (name "unconnected-(U2-HIBn-Pad51)") (class "Default")
      (node (ref "U2") (pin "51") (pinfunction "HIBn_51") (pintype "passive+no_connect"))
    )
    (net (code "86") (name "unconnected-(U2-PA7{slash}I2C1SDA-Pad35)") (class "Default")
      (node (ref "U2") (pin "35") (pinfunction "PA7/I2C1SDA_35") (pintype "passive"))
    )
    (net (code "87") (name "unconnected-(U2-PE4-Pad6)") (class "Default")
      (node (ref "U2") (pin "6") (pinfunction "PE4_6") (pintype "passive"))
    )
    (net (code "88") (name "unconnected-(U2-PE5-Pad5)") (class "Default")
      (node (ref "U2") (pin "5") (pinfunction "PE5_5") (pintype "passive"))
    )
    (net (code "89") (name "unconnected-(U2-PE6{slash}C1o-Pad2)") (class "Default")
      (node (ref "U2") (pin "2") (pinfunction "PE6/C1o_2") (pintype "passive"))
    )
    (net (code "90") (name "unconnected-(U2-VBAT-Pad55)") (class "Default")
      (node (ref "U2") (pin "55") (pinfunction "VBAT_55") (pintype "passive+no_connect"))
    )
    (net (code "91") (name "unconnected-(U2-XOSC0-Pad52)") (class "Default")
      (node (ref "U2") (pin "52") (pinfunction "XOSC0_52") (pintype "passive+no_connect"))
    )
    (net (code "92") (name "unconnected-(U2-XOSC1-Pad53)") (class "Default")
      (node (ref "U2") (pin "53") (pinfunction "XOSC1_53") (pintype "passive+no_connect"))
    )
  )
)
